# USB_Host.net
KiCad netlist of a schematic drawn in Altium Designer
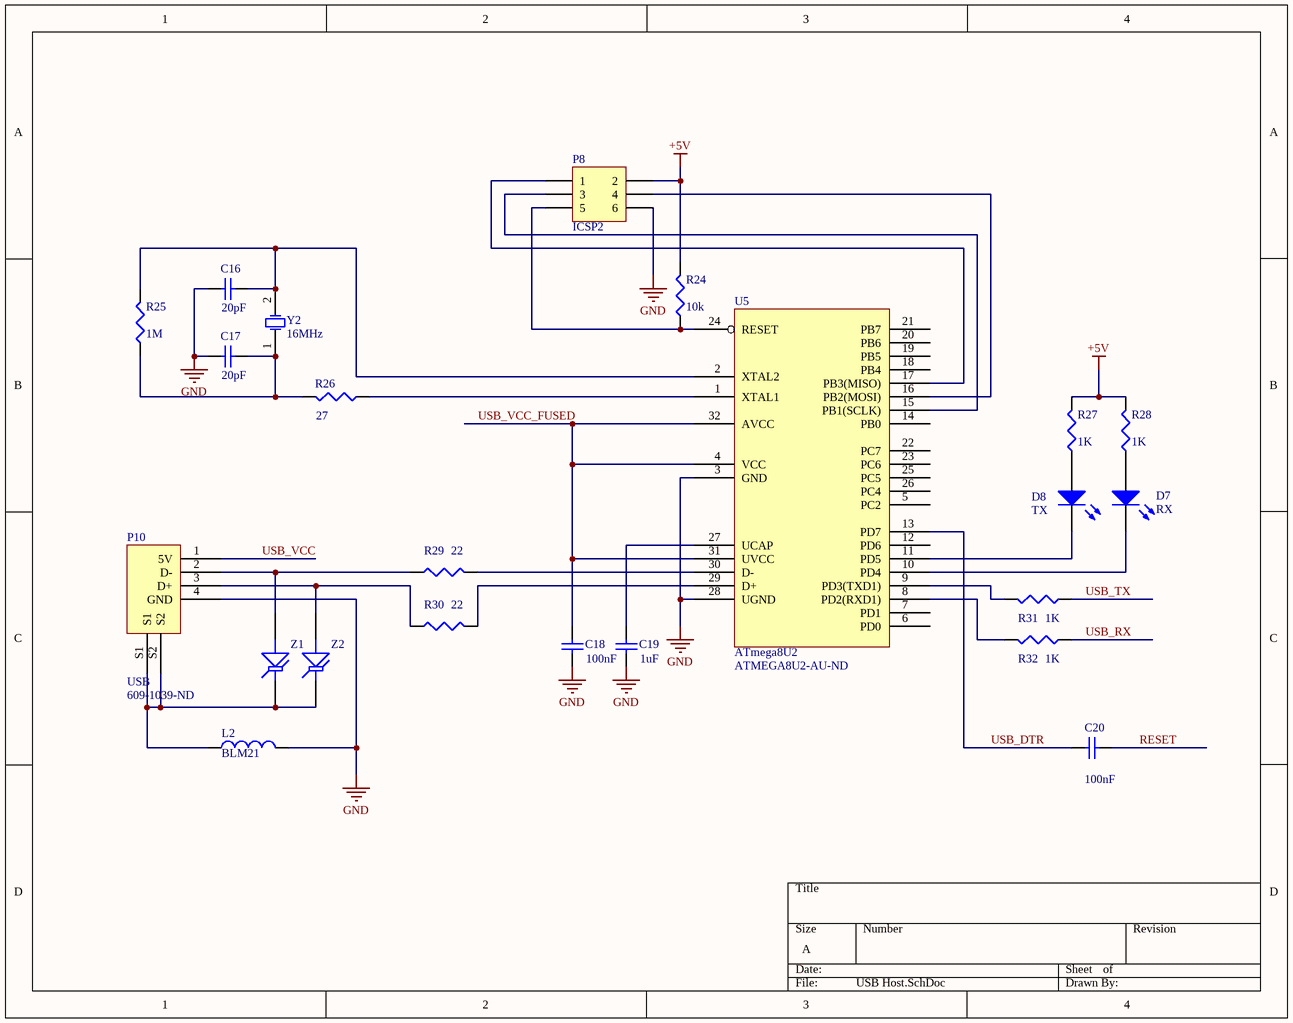
[diagram p0: USB Host.SchDoc]

(export (version "E")
  (design (tool "Eeschema 10.0.6"))
  (components
    (comp (ref "C16")
      (value "20pF")
      (footprint "C1206")
      (description "Capacitor (Semiconductor SIM Model)")
      (fields (field (name "Comment") "Cap Semi") (field (name "PUBLISHER") "Altium Limited"))
      (libsource (lib "Miscellaneous Devices") (part "Cap Semi"))
    )
    (comp (ref "C17")
      (value "20pF")
      (footprint "C1206")
      (description "Capacitor (Semiconductor SIM Model)")
      (fields (field (name "Comment") "Cap Semi") (field (name "PUBLISHER") "Altium Limited"))
      (libsource (lib "Miscellaneous Devices") (part "Cap Semi"))
    )
    (comp (ref "C18")
      (value "100nF")
      (footprint "C1206")
      (description "Capacitor (Semiconductor SIM Model)")
      (fields (field (name "Comment") "Cap Semi") (field (name "PUBLISHER") "Altium Limited"))
      (libsource (lib "Miscellaneous Devices") (part "Cap Semi"))
    )
    (comp (ref "C19")
      (value "1uF")
      (footprint "C1206")
      (description "Capacitor (Semiconductor SIM Model)")
      (fields (field (name "Comment") "Cap Semi") (field (name "PUBLISHER") "Altium Limited"))
      (libsource (lib "Miscellaneous Devices") (part "Cap Semi"))
    )
    (comp (ref "C20")
      (value "100nF")
      (footprint "C1206")
      (description "Capacitor (Semiconductor SIM Model)")
      (fields (field (name "Comment") "Cap Semi") (field (name "PUBLISHER") "Altium Limited"))
      (libsource (lib "Miscellaneous Devices") (part "Cap Semi"))
    )
    (comp (ref "D7")
      (value "RX")
      (footprint "HDR1X2")
      (description "Typical BLUE SiC LED")
      (fields (field (name "PUBLISHER") "Altium Limited"))
      (libsource (lib "Miscellaneous Devices") (part "LED3"))
    )
    (comp (ref "D8")
      (value "TX")
      (footprint "HDR1X2")
      (description "Typical BLUE SiC LED")
      (fields (field (name "PUBLISHER") "Altium Limited"))
      (libsource (lib "Miscellaneous Devices") (part "LED3"))
    )
    (comp (ref "L2")
      (value "BLM21")
      (footprint "INDC2012M")
      (description "Inductor")
      (fields (field (name "PUBLISHER") "Altium Limited"))
      (libsource (lib "Miscellaneous Devices") (part "Inductor"))
    )
    (comp (ref "P8")
      (value "ICSP2")
      (footprint "HDR2X3")
      (description "Header, 3-Pin, Dual row")
      (fields (field (name "PUBLISHER") "Altium Limited"))
      (libsource (lib "Miscellaneous Connectors") (part "Header 3X2"))
    )
    (comp (ref "P10")
      (value "USB")
      (footprint "USB-B PN61729")
      (fields (field (name "SUPPLIER PART NUMBER 1") "609-1039-ND"))
      (libsource (lib "Altium Footprints") (part "USB"))
    )
    (comp (ref "R24")
      (value "10k")
      (footprint "RESC3216M")
      (description "Resistor")
      (fields (field (name "Comment") "Res3") (field (name "PUBLISHER") "Altium Limited"))
      (libsource (lib "Miscellaneous Devices") (part "Res3"))
    )
    (comp (ref "R25")
      (value "1M")
      (footprint "RESC3216M")
      (description "Resistor")
      (fields (field (name "Comment") "Res3") (field (name "PUBLISHER") "Altium Limited"))
      (libsource (lib "Miscellaneous Devices") (part "Res3"))
    )
    (comp (ref "R26")
      (value "27")
      (footprint "RESC3216M")
      (description "Resistor")
      (fields (field (name "Comment") "Res3") (field (name "PUBLISHER") "Altium Limited"))
      (libsource (lib "Miscellaneous Devices") (part "Res3"))
    )
    (comp (ref "R27")
      (value "1K")
      (footprint "RESC3216M")
      (description "Resistor")
      (fields (field (name "Comment") "Res3") (field (name "PUBLISHER") "Altium Limited"))
      (libsource (lib "Miscellaneous Devices") (part "Res3"))
    )
    (comp (ref "R28")
      (value "1K")
      (footprint "RESC3216M")
      (description "Resistor")
      (fields (field (name "Comment") "Res3") (field (name "PUBLISHER") "Altium Limited"))
      (libsource (lib "Miscellaneous Devices") (part "Res3"))
    )
    (comp (ref "R29")
      (value "22")
      (footprint "RESC3216M")
      (description "Resistor")
      (fields (field (name "Comment") "Res3") (field (name "PUBLISHER") "Altium Limited"))
      (libsource (lib "Miscellaneous Devices") (part "Res3"))
    )
    (comp (ref "R30")
      (value "22")
      (footprint "RESC3216M")
      (description "Resistor")
      (fields (field (name "Comment") "Res3") (field (name "PUBLISHER") "Altium Limited"))
      (libsource (lib "Miscellaneous Devices") (part "Res3"))
    )
    (comp (ref "R31")
      (value "1K")
      (footprint "RESC3216M")
      (description "Resistor")
      (fields (field (name "Comment") "Res3") (field (name "PUBLISHER") "Altium Limited"))
      (libsource (lib "Miscellaneous Devices") (part "Res3"))
    )
    (comp (ref "R32")
      (value "1K")
      (footprint "RESC3216M")
      (description "Resistor")
      (fields (field (name "Comment") "Res3") (field (name "PUBLISHER") "Altium Limited"))
      (libsource (lib "Miscellaneous Devices") (part "Res3"))
    )
    (comp (ref "U5")
      (value "ATmega8U2")
      (footprint "QFP80P900X900-32M")
      (fields (field (name "SUPPLIER PART NUMBER 1") "ATMEGA8U2-AU-ND"))
      (libsource (lib "Altium Footprints") (part "ATmega8U2"))
    )
    (comp (ref "Y2")
      (value "16MHz")
      (footprint "SMT Crystal")
      (description "Crystal Oscillator")
      (fields (field (name "PUBLISHER") "Altium Limited"))
      (libsource (lib "Miscellaneous Devices") (part "XTAL"))
    )
    (comp (ref "Z1")
      (value "Tranzorb")
      (footprint "CD1608-0603")
      (description "Transient Voltage Suppression (TVS) Diode")
      (fields (field (name "PUBLISHER") "Altium Limited"))
      (libsource (lib "Miscellaneous Devices") (part "Tranzorb"))
    )
    (comp (ref "Z2")
      (value "Tranzorb")
      (footprint "CD1608-0603")
      (description "Transient Voltage Suppression (TVS) Diode")
      (fields (field (name "PUBLISHER") "Altium Limited"))
      (libsource (lib "Miscellaneous Devices") (part "Tranzorb"))
    )
  )
  (nets
    (net (code "1") (name "+5V") (class "Default")
      (node (ref "P8") (pin "2") (pinfunction "2_2") (pintype "passive"))
      (node (ref "R24") (pin "2") (pinfunction "2_2") (pintype "passive"))
      (node (ref "R27") (pin "2") (pinfunction "2_2") (pintype "passive"))
      (node (ref "R28") (pin "2") (pinfunction "2_2") (pintype "passive"))
    )
    (net (code "2") (name "/RESET") (class "Default")
      (node (ref "C20") (pin "2") (pinfunction "2_2") (pintype "passive"))
    )
    (net (code "3") (name "/USB_DTR") (class "Default")
      (node (ref "C20") (pin "1") (pinfunction "1_1") (pintype "passive"))
      (node (ref "U5") (pin "13") (pinfunction "PD7_13") (pintype "passive"))
    )
    (net (code "4") (name "/USB_RX") (class "Default")
      (node (ref "R32") (pin "1") (pinfunction "1_1") (pintype "passive"))
    )
    (net (code "5") (name "/USB_TX") (class "Default")
      (node (ref "R31") (pin "1") (pinfunction "1_1") (pintype "passive"))
    )
    (net (code "6") (name "/USB_VCC") (class "Default")
      (node (ref "P10") (pin "1") (pinfunction "5V_1") (pintype "passive"))
    )
    (net (code "7") (name "/USB_VCC_FUSED") (class "Default")
      (node (ref "C18") (pin "2") (pinfunction "2_2") (pintype "passive"))
      (node (ref "U5") (pin "31") (pinfunction "UVCC_31") (pintype "passive"))
      (node (ref "U5") (pin "32") (pinfunction "AVCC_32") (pintype "passive"))
      (node (ref "U5") (pin "4") (pinfunction "VCC_4") (pintype "passive"))
    )
    (net (code "8") (name "GND") (class "Default")
      (node (ref "C16") (pin "1") (pinfunction "1_1") (pintype "passive"))
      (node (ref "C17") (pin "2") (pinfunction "2_2") (pintype "passive"))
      (node (ref "C18") (pin "1") (pinfunction "1_1") (pintype "passive"))
      (node (ref "C19") (pin "1") (pinfunction "1_1") (pintype "passive"))
      (node (ref "L2") (pin "2") (pinfunction "2_2") (pintype "passive"))
      (node (ref "P10") (pin "4") (pinfunction "GND_4") (pintype "passive"))
      (node (ref "P8") (pin "6") (pinfunction "6_6") (pintype "passive"))
      (node (ref "U5") (pin "28") (pinfunction "UGND_28") (pintype "passive"))
      (node (ref "U5") (pin "3") (pinfunction "GND_3") (pintype "passive"))
    )
    (net (code "9") (name "Net-(D7-A)") (class "Default")
      (node (ref "D7") (pin "1") (pinfunction "A_1") (pintype "passive"))
      (node (ref "R28") (pin "1") (pinfunction "1_1") (pintype "passive"))
    )
    (net (code "10") (name "Net-(D7-K)") (class "Default")
      (node (ref "D7") (pin "2") (pinfunction "K_2") (pintype "passive"))
      (node (ref "U5") (pin "10") (pinfunction "PD4_10") (pintype "passive"))
    )
    (net (code "11") (name "Net-(D8-A)") (class "Default")
      (node (ref "D8") (pin "1") (pinfunction "A_1") (pintype "passive"))
      (node (ref "R27") (pin "1") (pinfunction "1_1") (pintype "passive"))
    )
    (net (code "12") (name "Net-(D8-K)") (class "Default")
      (node (ref "D8") (pin "2") (pinfunction "K_2") (pintype "passive"))
      (node (ref "U5") (pin "11") (pinfunction "PD5_11") (pintype "passive"))
    )
    (net (code "13") (name "Net-(P10-D+)") (class "Default")
      (node (ref "P10") (pin "3") (pinfunction "D+_3") (pintype "passive"))
      (node (ref "R30") (pin "1") (pinfunction "1_1") (pintype "passive"))
      (node (ref "Z2") (pin "1") (pinfunction "A_1") (pintype "passive"))
    )
    (net (code "14") (name "Net-(P10-D-)") (class "Default")
      (node (ref "P10") (pin "2") (pinfunction "D-_2") (pintype "passive"))
      (node (ref "R29") (pin "1") (pinfunction "1_1") (pintype "passive"))
      (node (ref "Z1") (pin "1") (pinfunction "A_1") (pintype "passive"))
    )
    (net (code "15") (name "Net-(U5-D+)") (class "Default")
      (node (ref "R30") (pin "2") (pinfunction "2_2") (pintype "passive"))
      (node (ref "U5") (pin "29") (pinfunction "D+_29") (pintype "passive"))
    )
    (net (code "16") (name "Net-(U5-D-)") (class "Default")
      (node (ref "R29") (pin "2") (pinfunction "2_2") (pintype "passive"))
      (node (ref "U5") (pin "30") (pinfunction "D-_30") (pintype "passive"))
    )
    (net (code "17") (name "Net-(U5-PB1(SCLK))") (class "Default")
      (node (ref "P8") (pin "3") (pinfunction "3_3") (pintype "passive"))
      (node (ref "U5") (pin "15") (pinfunction "PB1(SCLK)_15") (pintype "passive"))
    )
    (net (code "18") (name "Net-(U5-PB2(MOSI))") (class "Default")
      (node (ref "P8") (pin "4") (pinfunction "4_4") (pintype "passive"))
      (node (ref "U5") (pin "16") (pinfunction "PB2(MOSI)_16") (pintype "passive"))
    )
    (net (code "19") (name "Net-(U5-PB3(MISO))") (class "Default")
      (node (ref "P8") (pin "1") (pinfunction "1_1") (pintype "passive"))
      (node (ref "U5") (pin "17") (pinfunction "PB3(MISO)_17") (pintype "passive"))
    )
    (net (code "20") (name "Net-(U5-PD2(RXD1))") (class "Default")
      (node (ref "R32") (pin "2") (pinfunction "2_2") (pintype "passive"))
      (node (ref "U5") (pin "8") (pinfunction "PD2(RXD1)_8") (pintype "passive"))
    )
    (net (code "21") (name "Net-(U5-PD3(TXD1))") (class "Default")
      (node (ref "R31") (pin "2") (pinfunction "2_2") (pintype "passive"))
      (node (ref "U5") (pin "9") (pinfunction "PD3(TXD1)_9") (pintype "passive"))
    )
    (net (code "22") (name "Net-(U5-RESET)") (class "Default")
      (node (ref "P8") (pin "5") (pinfunction "5_5") (pintype "passive"))
      (node (ref "R24") (pin "1") (pinfunction "1_1") (pintype "passive"))
      (node (ref "U5") (pin "24") (pinfunction "RESET_24") (pintype "passive"))
    )
    (net (code "23") (name "Net-(U5-UCAP)") (class "Default")
      (node (ref "C19") (pin "2") (pinfunction "2_2") (pintype "passive"))
      (node (ref "U5") (pin "27") (pinfunction "UCAP_27") (pintype "passive"))
    )
    (net (code "24") (name "Net-(U5-XTAL1)") (class "Default")
      (node (ref "R26") (pin "1") (pinfunction "1_1") (pintype "passive"))
      (node (ref "U5") (pin "1") (pinfunction "XTAL1_1") (pintype "passive"))
    )
    (net (code "25") (name "Net-(U5-XTAL2)") (class "Default")
      (node (ref "C16") (pin "2") (pinfunction "2_2") (pintype "passive"))
      (node (ref "R25") (pin "2") (pinfunction "2_2") (pintype "passive"))
      (node (ref "U5") (pin "2") (pinfunction "XTAL2_2") (pintype "passive"))
      (node (ref "Y2") (pin "2") (pinfunction "OSC2_2") (pintype "passive"))
    )
    (net (code "26") (name "Net-(Y2-OSC1)") (class "Default")
      (node (ref "C17") (pin "1") (pinfunction "1_1") (pintype "passive"))
      (node (ref "R25") (pin "1") (pinfunction "1_1") (pintype "passive"))
      (node (ref "R26") (pin "2") (pinfunction "2_2") (pintype "passive"))
      (node (ref "Y2") (pin "1") (pinfunction "OSC1_1") (pintype "passive"))
    )
    (net (code "27") (name "Net-(Z1-K)") (class "Default")
      (node (ref "L2") (pin "1") (pinfunction "1_1") (pintype "passive"))
      (node (ref "P10") (pin "S1") (pinfunction "S1_S1") (pintype "passive"))
      (node (ref "P10") (pin "S2") (pinfunction "S2_S2") (pintype "passive"))
      (node (ref "Z1") (pin "2") (pinfunction "K_2") (pintype "passive"))
      (node (ref "Z2") (pin "2") (pinfunction "K_2") (pintype "passive"))
    )
    (net (code "28") (name "unconnected-(U5-PB0-Pad14)") (class "Default")
      (node (ref "U5") (pin "14") (pinfunction "PB0_14") (pintype "passive"))
    )
    (net (code "29") (name "unconnected-(U5-PB4-Pad18)") (class "Default")
      (node (ref "U5") (pin "18") (pinfunction "PB4_18") (pintype "passive"))
    )
    (net (code "30") (name "unconnected-(U5-PB5-Pad19)") (class "Default")
      (node (ref "U5") (pin "19") (pinfunction "PB5_19") (pintype "passive"))
    )
    (net (code "31") (name "unconnected-(U5-PB6-Pad20)") (class "Default")
      (node (ref "U5") (pin "20") (pinfunction "PB6_20") (pintype "passive"))
    )
    (net (code "32") (name "unconnected-(U5-PB7-Pad21)") (class "Default")
      (node (ref "U5") (pin "21") (pinfunction "PB7_21") (pintype "passive"))
    )
    (net (code "33") (name "unconnected-(U5-PC2-Pad5)") (class "Default")
      (node (ref "U5") (pin "5") (pinfunction "PC2_5") (pintype "passive"))
    )
    (net (code "34") (name "unconnected-(U5-PC4-Pad26)") (class "Default")
      (node (ref "U5") (pin "26") (pinfunction "PC4_26") (pintype "passive"))
    )
    (net (code "35") (name "unconnected-(U5-PC5-Pad25)") (class "Default")
      (node (ref "U5") (pin "25") (pinfunction "PC5_25") (pintype "passive"))
    )
    (net (code "36") (name "unconnected-(U5-PC6-Pad23)") (class "Default")
      (node (ref "U5") (pin "23") (pinfunction "PC6_23") (pintype "passive"))
    )
    (net (code "37") (name "unconnected-(U5-PC7-Pad22)") (class "Default")
      (node (ref "U5") (pin "22") (pinfunction "PC7_22") (pintype "passive"))
    )
    (net (code "38") (name "unconnected-(U5-PD0-Pad6)") (class "Default")
      (node (ref "U5") (pin "6") (pinfunction "PD0_6") (pintype "passive"))
    )
    (net (code "39") (name "unconnected-(U5-PD1-Pad7)") (class "Default")
      (node (ref "U5") (pin "7") (pinfunction "PD1_7") (pintype "passive"))
    )
    (net (code "40") (name "unconnected-(U5-PD6-Pad12)") (class "Default")
      (node (ref "U5") (pin "12") (pinfunction "PD6_12") (pintype "passive"))
    )
  )
)
